# Convector_digit.net
KiCad netlist of a schematic drawn in Altium Designer
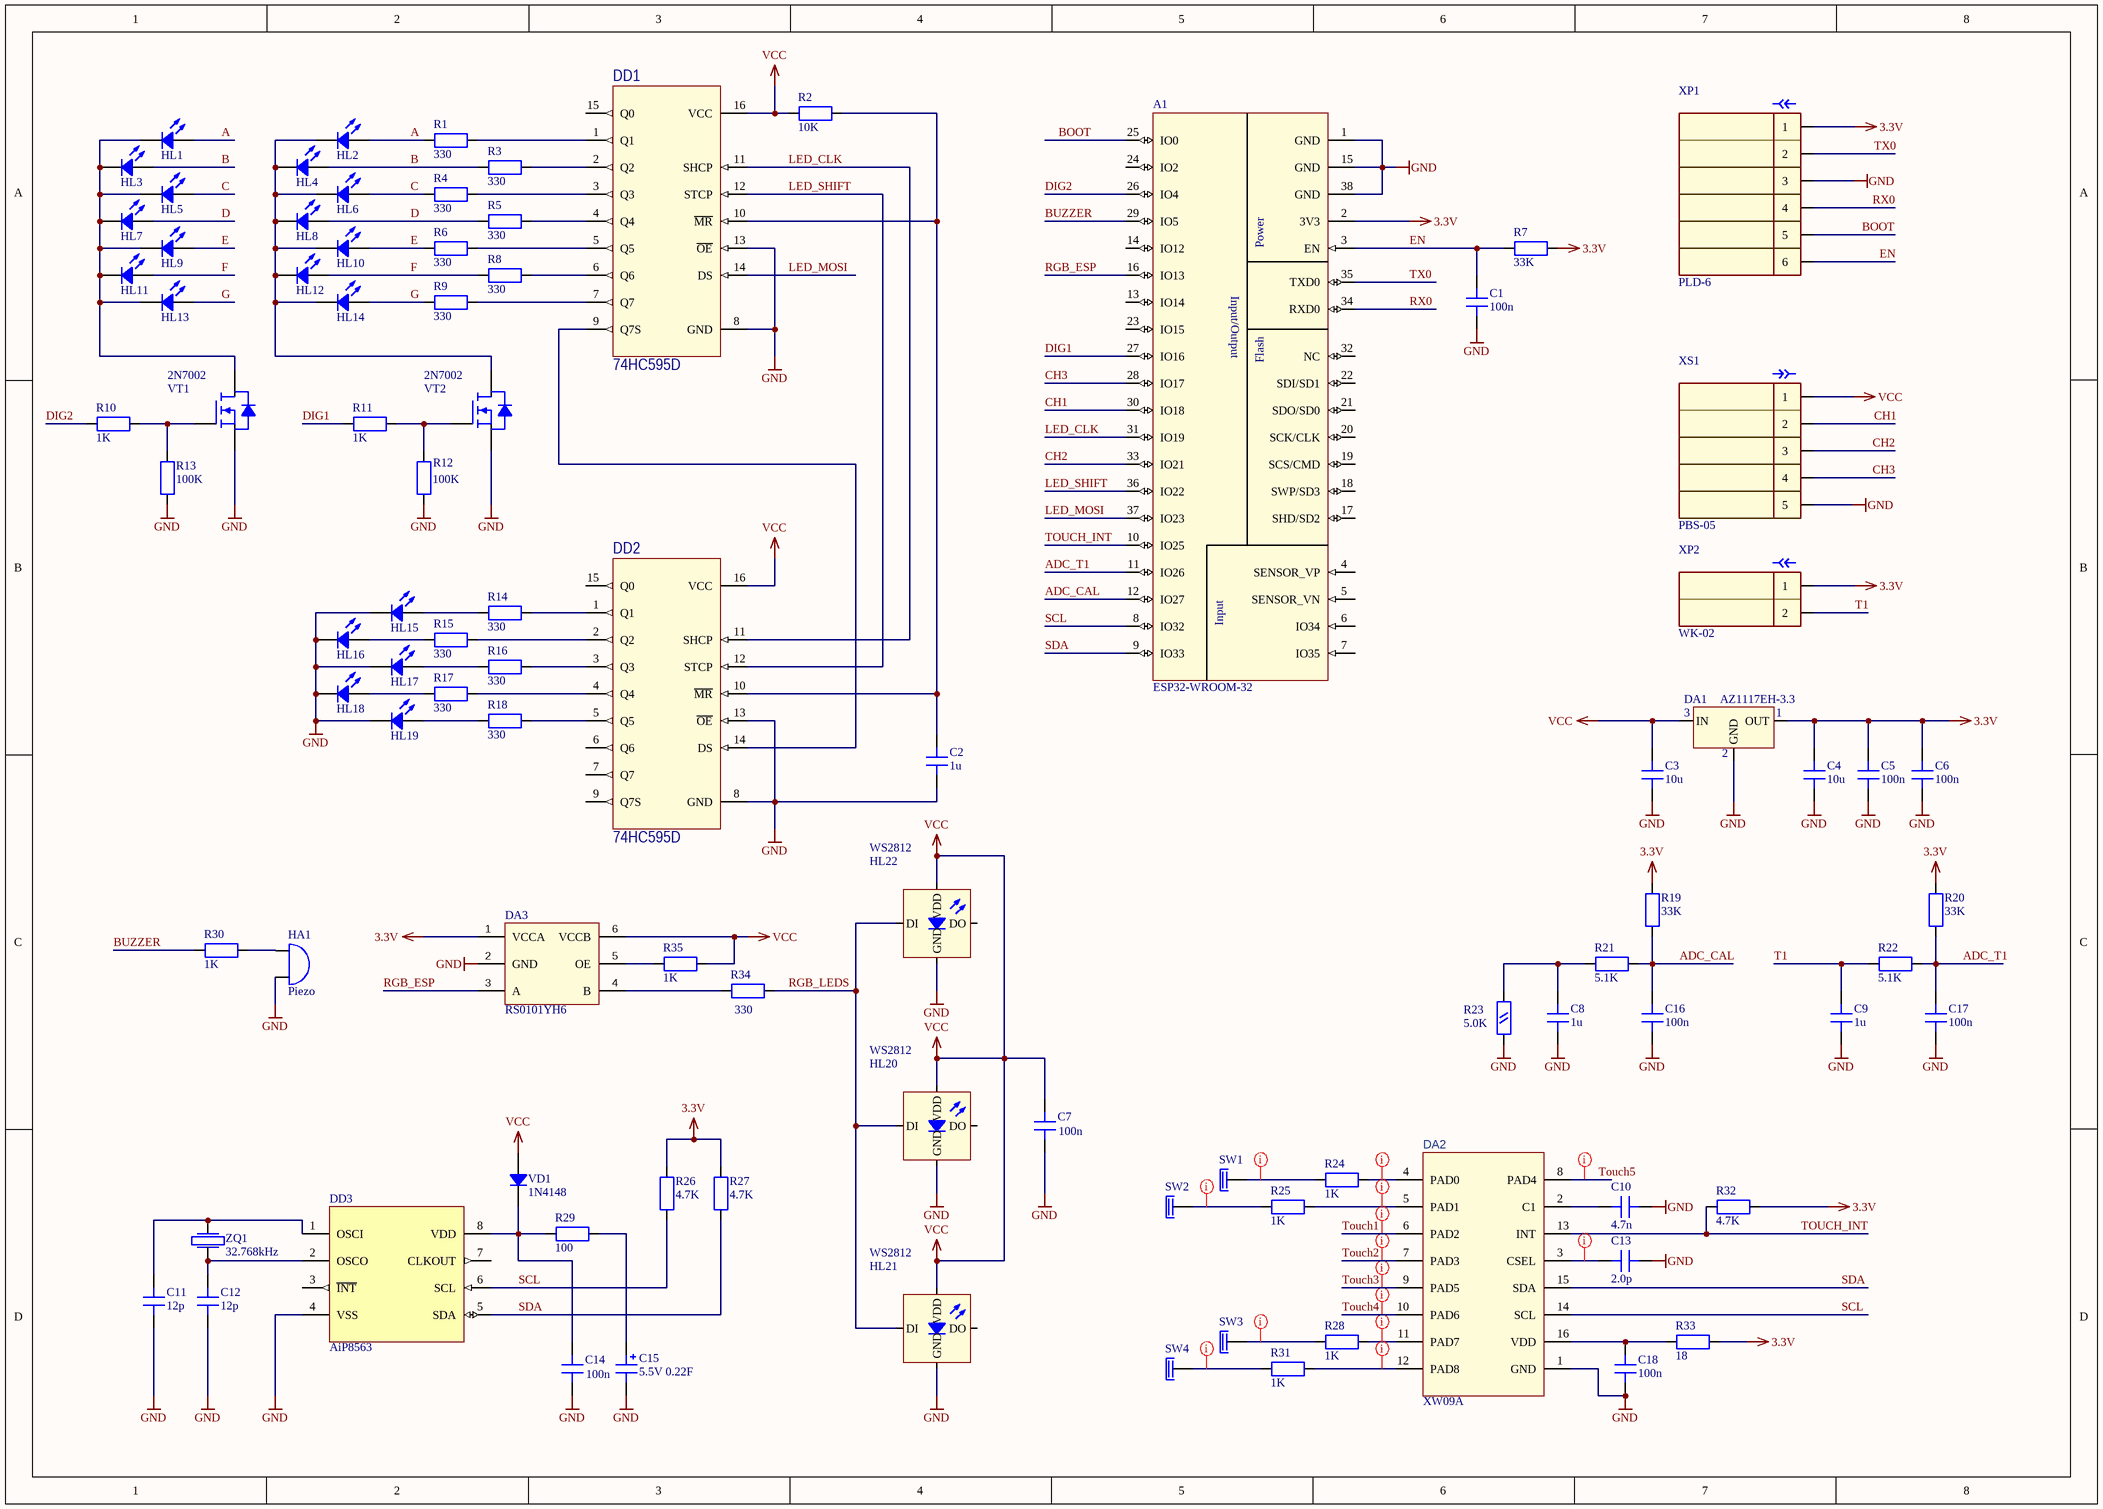
[diagram p0: Convector_digit.SchDoc]

(export (version "E")
  (design (tool "Eeschema 10.0.6"))
  (components
    (comp (ref "A1")
      (value "ESP32-WROOM-32")
      (footprint "ESP-WROOM-32")
      (fields (field (name "MANUFACTURER") "Espressif Systems"))
      (libsource (lib "IZTT_Library") (part "ESP32-WROOM-32"))
    )
    (comp (ref "C1")
      (value "100n")
      (footprint "C0603")
      (description "Cap Ceramic, 0603, ±10%, 50V, X7R (X5R), -55 +125C (-55 +85C)")
      (libsource (lib "IZTT_Library") (part "Capacitor"))
    )
    (comp (ref "C2")
      (value "1u")
      (footprint "C0603")
      (description "Cap Ceramic, 0603, ±10%, 50V, X7R (X5R), -55 +125C (-55 +85C)")
      (libsource (lib "IZTT_Library") (part "Capacitor"))
    )
    (comp (ref "C3")
      (value "10u")
      (footprint "C0805")
      (description "Cap Ceramic, 0805, ±10%, 50V, X7R (X5R), -55 +125C (-55 +85C)")
      (libsource (lib "IZTT_Library") (part "Capacitor"))
    )
    (comp (ref "C4")
      (value "10u")
      (footprint "C0805")
      (description "Cap Ceramic, 0805, ±10%, 50V, X7R (X5R), -55 +125C (-55 +85C)")
      (libsource (lib "IZTT_Library") (part "Capacitor"))
    )
    (comp (ref "C5")
      (value "100n")
      (footprint "C0603")
      (description "Cap Ceramic, 0603, ±10%, 50V, X7R (X5R), -55 +125C (-55 +85C)")
      (libsource (lib "IZTT_Library") (part "Capacitor"))
    )
    (comp (ref "C6")
      (value "100n")
      (footprint "C0603")
      (description "Cap Ceramic, 0603, ±10%, 50V, X7R (X5R), -55 +125C (-55 +85C)")
      (libsource (lib "IZTT_Library") (part "Capacitor"))
    )
    (comp (ref "C7")
      (value "100n")
      (footprint "C0603")
      (description "Cap Ceramic, 0603, ±10%, 50V, X7R (X5R), -55 +125C (-55 +85C)")
      (libsource (lib "IZTT_Library") (part "Capacitor"))
    )
    (comp (ref "C8")
      (value "1u")
      (footprint "C0603")
      (description "Cap Ceramic, 0603, ±10%, 50V, X7R (X5R), -55 +125C (-55 +85C)")
      (libsource (lib "IZTT_Library") (part "Capacitor"))
    )
    (comp (ref "C9")
      (value "1u")
      (footprint "C0603")
      (description "Cap Ceramic, 0603, ±10%, 50V, X7R (X5R), -55 +125C (-55 +85C)")
      (libsource (lib "IZTT_Library") (part "Capacitor"))
    )
    (comp (ref "C10")
      (value "4.7n")
      (footprint "C0603")
      (description "Cap Ceramic, 0603, ±10%, 50V, X7R (X5R), -55 +125C (-55 +85C)")
      (libsource (lib "IZTT_Library") (part "Capacitor"))
    )
    (comp (ref "C11")
      (value "12p")
      (footprint "C0603")
      (description "Cap Ceramic, 0603, 5%, 50V, NPO (C0G), -55 +125C")
      (libsource (lib "IZTT_Library") (part "Capacitor"))
    )
    (comp (ref "C12")
      (value "12p")
      (footprint "C0603")
      (description "Cap Ceramic, 0603, 5%, 50V, NPO (C0G), -55 +125C")
      (libsource (lib "IZTT_Library") (part "Capacitor"))
    )
    (comp (ref "C13")
      (value "2.0p")
      (footprint "C0603")
      (description "Cap Ceramic, 0603, 5%, 50V, NPO (C0G), -55 +125C")
      (libsource (lib "IZTT_Library") (part "Capacitor"))
    )
    (comp (ref "C14")
      (value "100n")
      (footprint "C0603")
      (description "Cap Ceramic, 0603, ±10%, 50V, X7R (X5R), -55 +125C (-55 +85C)")
      (libsource (lib "IZTT_Library") (part "Capacitor"))
    )
    (comp (ref "C15")
      (value "5.5V 0.22F")
      (footprint "1207H")
      (description "Ionistor 5.5V 0.22F")
      (fields (field (name "MANUFACTURER") "WTSCAP (Wenting)"))
      (libsource (lib "IZTT_Library") (part "Capacitor_polarised"))
    )
    (comp (ref "C16")
      (value "100n")
      (footprint "C0603")
      (description "Cap Ceramic, 0603, ±10%, 50V, X7R (X5R), -55 +125C (-55 +85C)")
      (libsource (lib "IZTT_Library") (part "Capacitor"))
    )
    (comp (ref "C17")
      (value "100n")
      (footprint "C0603")
      (description "Cap Ceramic, 0603, ±10%, 50V, X7R (X5R), -55 +125C (-55 +85C)")
      (libsource (lib "IZTT_Library") (part "Capacitor"))
    )
    (comp (ref "C18")
      (value "100n")
      (footprint "C0603")
      (description "Cap Ceramic, 0603, ±10%, 50V, X7R (X5R), -55 +125C (-55 +85C)")
      (libsource (lib "IZTT_Library") (part "Capacitor"))
    )
    (comp (ref "DA1")
      (value "AZ1117EH-3.3")
      (footprint "SOT-223")
      (description "IC, Vreg, LDO, For Low ESR MLCC Cout, SOT223")
      (libsource (lib "IZTT_Library") (part "LDO_1117"))
    )
    (comp (ref "DA2")
      (value "XW09A")
      (footprint "SO-16")
      (description "SOP-16 Touch Screen Controller ICs RoHS")
      (fields (field (name "MANUFACTURER") "Sam&wing") (field (name "LCSC_PARTNUMBER") "C441720"))
      (libsource (lib "IZTT_Library") (part "XW09X"))
    )
    (comp (ref "DA3")
      (value "RS0101YH6")
      (footprint "SOT-23-6")
      (description "Level Translators, Shifters RoHS")
      (fields (field (name "MANUFACTURER") "Jiangsu RUNIC Tech"))
      (libsource (lib "IZTT_Library") (part "RS0101YH6"))
    )
    (comp (ref "DD1")
      (value "74HC595D")
      (footprint "SO-16")
      (description "Shift Register Serial to parallel, serial SOIC-16_150mil")
      (fields (field (name "MANUFACTURER") "Shenzhen Fuman Elec"))
      (libsource (lib "IZTT_Library") (part "74HC595D"))
    )
    (comp (ref "DD2")
      (value "74HC595D")
      (footprint "SO-16")
      (description "Shift Register Serial to parallel, serial SOIC-16_150mil")
      (fields (field (name "MANUFACTURER") "Shenzhen Fuman Elec"))
      (libsource (lib "IZTT_Library") (part "74HC595D"))
    )
    (comp (ref "DD3")
      (value "AiP8563")
      (footprint "SO-8")
      (description "SOP-8 Real-time Clocks RoHS")
      (fields (field (name "MANUFACTURER") "Wuxi I-core Elec"))
      (libsource (lib "IZTT_Library") (part "AiP8563"))
    )
    (comp (ref "HA1")
      (value "Piezo")
      (footprint "PS1240P02BT")
      (description "BUZZER, Piezo, Pitch 5mm (TDK)")
      (libsource (lib "IZTT_Library") (part "Buzzer"))
    )
    (comp (ref "HL1")
      (value "0603 White")
      (footprint "LED0603Y")
      (description "LED, SMD 0603, 30mA, White")
      (fields (field (name "MANUFACTURER") "Orient"))
      (libsource (lib "IZTT_Library") (part "LED"))
    )
    (comp (ref "HL2")
      (value "0603 White")
      (footprint "LED0603Y")
      (description "LED, SMD 0603, 30mA, White")
      (fields (field (name "MANUFACTURER") "Orient"))
      (libsource (lib "IZTT_Library") (part "LED"))
    )
    (comp (ref "HL3")
      (value "0603 White")
      (footprint "LED0603Y")
      (description "LED, SMD 0603, 30mA, White")
      (fields (field (name "MANUFACTURER") "Orient"))
      (libsource (lib "IZTT_Library") (part "LED"))
    )
    (comp (ref "HL4")
      (value "0603 White")
      (footprint "LED0603Y")
      (description "LED, SMD 0603, 30mA, White")
      (fields (field (name "MANUFACTURER") "Orient"))
      (libsource (lib "IZTT_Library") (part "LED"))
    )
    (comp (ref "HL5")
      (value "0603 White")
      (footprint "LED0603Y")
      (description "LED, SMD 0603, 30mA, White")
      (fields (field (name "MANUFACTURER") "Orient"))
      (libsource (lib "IZTT_Library") (part "LED"))
    )
    (comp (ref "HL6")
      (value "0603 White")
      (footprint "LED0603Y")
      (description "LED, SMD 0603, 30mA, White")
      (fields (field (name "MANUFACTURER") "Orient"))
      (libsource (lib "IZTT_Library") (part "LED"))
    )
    (comp (ref "HL7")
      (value "0603 White")
      (footprint "LED0603Y")
      (description "LED, SMD 0603, 30mA, White")
      (fields (field (name "MANUFACTURER") "Orient"))
      (libsource (lib "IZTT_Library") (part "LED"))
    )
    (comp (ref "HL8")
      (value "0603 White")
      (footprint "LED0603Y")
      (description "LED, SMD 0603, 30mA, White")
      (fields (field (name "MANUFACTURER") "Orient"))
      (libsource (lib "IZTT_Library") (part "LED"))
    )
    (comp (ref "HL9")
      (value "0603 White")
      (footprint "LED0603Y")
      (description "LED, SMD 0603, 30mA, White")
      (fields (field (name "MANUFACTURER") "Orient"))
      (libsource (lib "IZTT_Library") (part "LED"))
    )
    (comp (ref "HL10")
      (value "0603 White")
      (footprint "LED0603Y")
      (description "LED, SMD 0603, 30mA, White")
      (fields (field (name "MANUFACTURER") "Orient"))
      (libsource (lib "IZTT_Library") (part "LED"))
    )
    (comp (ref "HL11")
      (value "0603 White")
      (footprint "LED0603Y")
      (description "LED, SMD 0603, 30mA, White")
      (fields (field (name "MANUFACTURER") "Orient"))
      (libsource (lib "IZTT_Library") (part "LED"))
    )
    (comp (ref "HL12")
      (value "0603 White")
      (footprint "LED0603Y")
      (description "LED, SMD 0603, 30mA, White")
      (fields (field (name "MANUFACTURER") "Orient"))
      (libsource (lib "IZTT_Library") (part "LED"))
    )
    (comp (ref "HL13")
      (value "0603 White")
      (footprint "LED0603Y")
      (description "LED, SMD 0603, 30mA, White")
      (fields (field (name "MANUFACTURER") "Orient"))
      (libsource (lib "IZTT_Library") (part "LED"))
    )
    (comp (ref "HL14")
      (value "0603 White")
      (footprint "LED0603Y")
      (description "LED, SMD 0603, 30mA, White")
      (fields (field (name "MANUFACTURER") "Orient"))
      (libsource (lib "IZTT_Library") (part "LED"))
    )
    (comp (ref "HL15")
      (value "0603 White")
      (footprint "LED0603Y")
      (description "LED, SMD 0603, 30mA, White")
      (fields (field (name "MANUFACTURER") "Orient"))
      (libsource (lib "IZTT_Library") (part "LED"))
    )
    (comp (ref "HL16")
      (value "0603 White")
      (footprint "LED0603Y")
      (description "LED, SMD 0603, 30mA, White")
      (fields (field (name "MANUFACTURER") "Orient"))
      (libsource (lib "IZTT_Library") (part "LED"))
    )
    (comp (ref "HL17")
      (value "0603 White")
      (footprint "LED0603Y")
      (description "LED, SMD 0603, 30mA, White")
      (fields (field (name "MANUFACTURER") "Orient"))
      (libsource (lib "IZTT_Library") (part "LED"))
    )
    (comp (ref "HL18")
      (value "0603 White")
      (footprint "LED0603Y")
      (description "LED, SMD 0603, 30mA, White")
      (fields (field (name "MANUFACTURER") "Orient"))
      (libsource (lib "IZTT_Library") (part "LED"))
    )
    (comp (ref "HL19")
      (value "0603 White")
      (footprint "LED0603Y")
      (description "LED, SMD 0603, 30mA, White")
      (fields (field (name "MANUFACTURER") "Orient"))
      (libsource (lib "IZTT_Library") (part "LED"))
    )
    (comp (ref "HL20")
      (value "WS2812")
      (footprint "WS2812C-2020")
      (description "Intelligent control LED, 2.0x2.0mm")
      (fields (field (name "MANUFACTURER") "Worldsemi"))
      (libsource (lib "IZTT_Library") (part "WS2812C-2020"))
    )
    (comp (ref "HL21")
      (value "WS2812")
      (footprint "WS2812C-2020")
      (description "Intelligent control LED, 2.0x2.0mm")
      (fields (field (name "MANUFACTURER") "Worldsemi"))
      (libsource (lib "IZTT_Library") (part "WS2812C-2020"))
    )
    (comp (ref "HL22")
      (value "WS2812")
      (footprint "WS2812C-2020")
      (description "Intelligent control LED, 2.0x2.0mm")
      (fields (field (name "MANUFACTURER") "Worldsemi"))
      (libsource (lib "IZTT_Library") (part "WS2812C-2020"))
    )
    (comp (ref "R1")
      (value "330")
      (footprint "R0603")
      (description "Res, 0603, 1%, 1/10W")
      (fields (field (name "MANUFACTURER") "Walsin Tech Corp"))
      (libsource (lib "IZTT_Library") (part "Resistor"))
    )
    (comp (ref "R2")
      (value "10K")
      (footprint "R0603")
      (description "Res, 0603, 1%, 1/10W")
      (fields (field (name "MANUFACTURER") "FH(Guangdong Fenghua Advanced Tech)"))
      (libsource (lib "IZTT_Library") (part "Resistor"))
    )
    (comp (ref "R3")
      (value "330")
      (footprint "R0603")
      (description "Res, 0603, 1%, 1/10W")
      (fields (field (name "MANUFACTURER") "Walsin Tech Corp"))
      (libsource (lib "IZTT_Library") (part "Resistor"))
    )
    (comp (ref "R4")
      (value "330")
      (footprint "R0603")
      (description "Res, 0603, 1%, 1/10W")
      (fields (field (name "MANUFACTURER") "Walsin Tech Corp"))
      (libsource (lib "IZTT_Library") (part "Resistor"))
    )
    (comp (ref "R5")
      (value "330")
      (footprint "R0603")
      (description "Res, 0603, 1%, 1/10W")
      (fields (field (name "MANUFACTURER") "Walsin Tech Corp"))
      (libsource (lib "IZTT_Library") (part "Resistor"))
    )
    (comp (ref "R6")
      (value "330")
      (footprint "R0603")
      (description "Res, 0603, 1%, 1/10W")
      (fields (field (name "MANUFACTURER") "Walsin Tech Corp"))
      (libsource (lib "IZTT_Library") (part "Resistor"))
    )
    (comp (ref "R7")
      (value "33K")
      (footprint "R0603")
      (description "Res, 0603, 1%, 1/10W")
      (fields (field (name "MANUFACTURER") "UNI-ROYAL(Uniroyal Elec)"))
      (libsource (lib "IZTT_Library") (part "Resistor"))
    )
    (comp (ref "R8")
      (value "330")
      (footprint "R0603")
      (description "Res, 0603, 1%, 1/10W")
      (fields (field (name "MANUFACTURER") "Walsin Tech Corp"))
      (libsource (lib "IZTT_Library") (part "Resistor"))
    )
    (comp (ref "R9")
      (value "330")
      (footprint "R0603")
      (description "Res, 0603, 1%, 1/10W")
      (fields (field (name "MANUFACTURER") "Walsin Tech Corp"))
      (libsource (lib "IZTT_Library") (part "Resistor"))
    )
    (comp (ref "R10")
      (value "1K")
      (footprint "R0603")
      (description "Res, 0603, 1%, 1/10W")
      (fields (field (name "MANUFACTURER") "FH(Guangdong Fenghua Advanced Tech)"))
      (libsource (lib "IZTT_Library") (part "Resistor"))
    )
    (comp (ref "R11")
      (value "1K")
      (footprint "R0603")
      (description "Res, 0603, 1%, 1/10W")
      (fields (field (name "MANUFACTURER") "FH(Guangdong Fenghua Advanced Tech)"))
      (libsource (lib "IZTT_Library") (part "Resistor"))
    )
    (comp (ref "R12")
      (value "100K")
      (footprint "R0603")
      (description "Res, 0603, 1%, 1/10W")
      (fields (field (name "MANUFACTURER") "UNI-ROYAL(Uniroyal Elec)"))
      (libsource (lib "IZTT_Library") (part "Resistor"))
    )
    (comp (ref "R13")
      (value "100K")
      (footprint "R0603")
      (description "Res, 0603, 1%, 1/10W")
      (fields (field (name "MANUFACTURER") "UNI-ROYAL(Uniroyal Elec)"))
      (libsource (lib "IZTT_Library") (part "Resistor"))
    )
    (comp (ref "R14")
      (value "330")
      (footprint "R0603")
      (description "Res, 0603, 1%, 1/10W")
      (fields (field (name "MANUFACTURER") "Walsin Tech Corp"))
      (libsource (lib "IZTT_Library") (part "Resistor"))
    )
    (comp (ref "R15")
      (value "330")
      (footprint "R0603")
      (description "Res, 0603, 1%, 1/10W")
      (fields (field (name "MANUFACTURER") "Walsin Tech Corp"))
      (libsource (lib "IZTT_Library") (part "Resistor"))
    )
    (comp (ref "R16")
      (value "330")
      (footprint "R0603")
      (description "Res, 0603, 1%, 1/10W")
      (fields (field (name "MANUFACTURER") "Walsin Tech Corp"))
      (libsource (lib "IZTT_Library") (part "Resistor"))
    )
    (comp (ref "R17")
      (value "330")
      (footprint "R0603")
      (description "Res, 0603, 1%, 1/10W")
      (fields (field (name "MANUFACTURER") "Walsin Tech Corp"))
      (libsource (lib "IZTT_Library") (part "Resistor"))
    )
    (comp (ref "R18")
      (value "330")
      (footprint "R0603")
      (description "Res, 0603, 1%, 1/10W")
      (fields (field (name "MANUFACTURER") "Walsin Tech Corp"))
      (libsource (lib "IZTT_Library") (part "Resistor"))
    )
    (comp (ref "R19")
      (value "33K")
      (footprint "R0603")
      (description "Res, 0603, 1%, 1/10W")
      (fields (field (name "MANUFACTURER") "UNI-ROYAL(Uniroyal Elec)"))
      (libsource (lib "IZTT_Library") (part "Resistor"))
    )
    (comp (ref "R20")
      (value "33K")
      (footprint "R0603")
      (description "Res, 0603, 1%, 1/10W")
      (fields (field (name "MANUFACTURER") "UNI-ROYAL(Uniroyal Elec)"))
      (libsource (lib "IZTT_Library") (part "Resistor"))
    )
    (comp (ref "R21")
      (value "5.1K")
      (footprint "R0603")
      (description "Res, 0603, 1%, 1/10W")
      (libsource (lib "IZTT_Library") (part "Resistor"))
    )
    (comp (ref "R22")
      (value "5.1K")
      (footprint "R0603")
      (description "Res, 0603, 1%, 1/10W")
      (libsource (lib "IZTT_Library") (part "Resistor"))
    )
    (comp (ref "R23")
      (value "5.0K")
      (footprint "R0805")
      (description "Res, 0805, 0.1%, 1/8W")
      (libsource (lib "IZTT_Library") (part "Resistor_1/8W"))
    )
    (comp (ref "R24")
      (value "1K")
      (footprint "R0603")
      (description "Res, 0603, 1%, 1/10W")
      (fields (field (name "MANUFACTURER") "FH(Guangdong Fenghua Advanced Tech)"))
      (libsource (lib "IZTT_Library") (part "Resistor"))
    )
    (comp (ref "R25")
      (value "1K")
      (footprint "R0603")
      (description "Res, 0603, 1%, 1/10W")
      (fields (field (name "MANUFACTURER") "FH(Guangdong Fenghua Advanced Tech)"))
      (libsource (lib "IZTT_Library") (part "Resistor"))
    )
    (comp (ref "R26")
      (value "4.7K")
      (footprint "R0603")
      (description "Res, 0603, 1%, 1/10W")
      (fields (field (name "MANUFACTURER") "UNI-ROYAL(Uniroyal Elec)"))
      (libsource (lib "IZTT_Library") (part "Resistor"))
    )
    (comp (ref "R27")
      (value "4.7K")
      (footprint "R0603")
      (description "Res, 0603, 1%, 1/10W")
      (fields (field (name "MANUFACTURER") "UNI-ROYAL(Uniroyal Elec)"))
      (libsource (lib "IZTT_Library") (part "Resistor"))
    )
    (comp (ref "R28")
      (value "1K")
      (footprint "R0603")
      (description "Res, 0603, 1%, 1/10W")
      (fields (field (name "MANUFACTURER") "FH(Guangdong Fenghua Advanced Tech)"))
      (libsource (lib "IZTT_Library") (part "Resistor"))
    )
    (comp (ref "R29")
      (value "100")
      (footprint "R0603")
      (description "Res, 0603, 1%, 1/10W")
      (fields (field (name "MANUFACTURER") "UNI-ROYAL(Uniroyal Elec)"))
      (libsource (lib "IZTT_Library") (part "Resistor"))
    )
    (comp (ref "R30")
      (value "1K")
      (footprint "R0603")
      (description "Res, 0603, 1%, 1/10W")
      (fields (field (name "MANUFACTURER") "FH(Guangdong Fenghua Advanced Tech)"))
      (libsource (lib "IZTT_Library") (part "Resistor"))
    )
    (comp (ref "R31")
      (value "1K")
      (footprint "R0603")
      (description "Res, 0603, 1%, 1/10W")
      (fields (field (name "MANUFACTURER") "FH(Guangdong Fenghua Advanced Tech)"))
      (libsource (lib "IZTT_Library") (part "Resistor"))
    )
    (comp (ref "R32")
      (value "4.7K")
      (footprint "R0603")
      (description "Res, 0603, 1%, 1/10W")
      (fields (field (name "MANUFACTURER") "UNI-ROYAL(Uniroyal Elec)"))
      (libsource (lib "IZTT_Library") (part "Resistor"))
    )
    (comp (ref "R33")
      (value "18")
      (footprint "R0603")
      (description "Res, 0603, 1%, 1/10W")
      (libsource (lib "IZTT_Library") (part "Resistor"))
    )
    (comp (ref "R34")
      (value "330")
      (footprint "R0603")
      (description "Res, 0603, 1%, 1/10W")
      (fields (field (name "MANUFACTURER") "Walsin Tech Corp"))
      (libsource (lib "IZTT_Library") (part "Resistor"))
    )
    (comp (ref "R35")
      (value "1K")
      (footprint "R0603")
      (description "Res, 0603, 1%, 1/10W")
      (fields (field (name "MANUFACTURER") "FH(Guangdong Fenghua Advanced Tech)"))
      (libsource (lib "IZTT_Library") (part "Resistor"))
    )
    (comp (ref "SW1")
      (value "XL-2258")
      (footprint "XL-2258")
      (description "Sensor Spring D=5.5/8.5, H=8.5±0.5mm")
      (libsource (lib "IZTT_Library") (part "SENSOR_SPRING"))
    )
    (comp (ref "SW2")
      (value "XL-2258")
      (footprint "XL-2258")
      (description "Sensor Spring D=5.5/8.5, H=8.5±0.5mm")
      (libsource (lib "IZTT_Library") (part "SENSOR_SPRING"))
    )
    (comp (ref "SW3")
      (value "XL-2258")
      (footprint "XL-2258")
      (description "Sensor Spring D=5.5/8.5, H=8.5±0.5mm")
      (libsource (lib "IZTT_Library") (part "SENSOR_SPRING"))
    )
    (comp (ref "SW4")
      (value "XL-2258")
      (footprint "XL-2258")
      (description "Sensor Spring D=5.5/8.5, H=8.5±0.5mm")
      (libsource (lib "IZTT_Library") (part "SENSOR_SPRING"))
    )
    (comp (ref "VD1")
      (value "1N4148")
      (footprint "SOD-323_DIODE")
      (description "Small Signal Fast Switching Diode, 150mA, 75V")
      (libsource (lib "IZTT_Library") (part "Diode"))
    )
    (comp (ref "VT1")
      (value "2N7002")
      (footprint "SOT-23-3")
      (description "HEXFET Power MOSFET N-CH")
      (libsource (lib "IZTT_Library") (part "N-MOS"))
    )
    (comp (ref "VT2")
      (value "2N7002")
      (footprint "SOT-23-3")
      (description "HEXFET Power MOSFET N-CH")
      (libsource (lib "IZTT_Library") (part "N-MOS"))
    )
    (comp (ref "XP1")
      (value "PLD-6")
      (footprint "PLD-6")
      (description "2x3 Male pld pins 2.54")
      (libsource (lib "IZTT_Library") (part "MALE_6PIN"))
    )
    (comp (ref "XP2")
      (value "WK-02")
      (footprint "WK-02")
      (description "Through-hole type shrouded header, XH Series, 2.5mm")
      (libsource (lib "IZTT_Library") (part "MALE_2PIN"))
    )
    (comp (ref "XS1")
      (value "PBS-05")
      (footprint "PBS-05")
      (description "Through-hole type shrouded header, XH Series, 2.5mm")
      (libsource (lib "IZTT_Library") (part "FEMALE_5PIN"))
    )
    (comp (ref "ZQ1")
      (value "32.768kHz")
      (footprint "KX-327NHT")
      (description "Quartz 32.768kHz 12.5pF 20ppm")
      (libsource (lib "IZTT_Library") (part "QUARTZ"))
    )
  )
  (nets
    (net (code "1") (name "/A") (class "Default")
      (node (ref "HL1") (pin "A") (pinfunction "A_A") (pintype "passive"))
      (node (ref "HL2") (pin "A") (pinfunction "A_A") (pintype "passive"))
      (node (ref "R1") (pin "1") (pinfunction "1_1") (pintype "passive"))
    )
    (net (code "2") (name "/ADC_CAL") (class "Default")
      (node (ref "A1") (pin "12") (pinfunction "IO27_12") (pintype "bidirectional"))
      (node (ref "C16") (pin "2") (pinfunction "2_2") (pintype "passive"))
      (node (ref "R19") (pin "1") (pinfunction "1_1") (pintype "passive"))
      (node (ref "R21") (pin "2") (pinfunction "2_2") (pintype "passive"))
    )
    (net (code "3") (name "/ADC_T1") (class "Default")
      (node (ref "A1") (pin "11") (pinfunction "IO26_11") (pintype "bidirectional"))
      (node (ref "C17") (pin "2") (pinfunction "2_2") (pintype "passive"))
      (node (ref "R20") (pin "1") (pinfunction "1_1") (pintype "passive"))
      (node (ref "R22") (pin "2") (pinfunction "2_2") (pintype "passive"))
    )
    (net (code "4") (name "/B") (class "Default")
      (node (ref "HL3") (pin "A") (pinfunction "A_A") (pintype "passive"))
      (node (ref "HL4") (pin "A") (pinfunction "A_A") (pintype "passive"))
      (node (ref "R3") (pin "1") (pinfunction "1_1") (pintype "passive"))
    )
    (net (code "5") (name "/BOOT") (class "Default")
      (node (ref "A1") (pin "25") (pinfunction "IO0_25") (pintype "bidirectional"))
      (node (ref "XP1") (pin "5") (pinfunction "5_5") (pintype "passive"))
    )
    (net (code "6") (name "/BUZZER") (class "Default")
      (node (ref "A1") (pin "29") (pinfunction "IO5_29") (pintype "bidirectional"))
      (node (ref "R30") (pin "2") (pinfunction "2_2") (pintype "passive"))
    )
    (net (code "7") (name "/C") (class "Default")
      (node (ref "HL5") (pin "A") (pinfunction "A_A") (pintype "passive"))
      (node (ref "HL6") (pin "A") (pinfunction "A_A") (pintype "passive"))
      (node (ref "R4") (pin "1") (pinfunction "1_1") (pintype "passive"))
    )
    (net (code "8") (name "/CH1") (class "Default")
      (node (ref "A1") (pin "30") (pinfunction "IO18_30") (pintype "bidirectional"))
      (node (ref "XS1") (pin "2") (pinfunction "2_2") (pintype "passive"))
    )
    (net (code "9") (name "/CH2") (class "Default")
      (node (ref "A1") (pin "33") (pinfunction "IO21_33") (pintype "bidirectional"))
      (node (ref "XS1") (pin "3") (pinfunction "3_3") (pintype "passive"))
    )
    (net (code "10") (name "/CH3") (class "Default")
      (node (ref "A1") (pin "28") (pinfunction "IO17_28") (pintype "bidirectional"))
      (node (ref "XS1") (pin "4") (pinfunction "4_4") (pintype "passive"))
    )
    (net (code "11") (name "/D") (class "Default")
      (node (ref "HL7") (pin "A") (pinfunction "A_A") (pintype "passive"))
      (node (ref "HL8") (pin "A") (pinfunction "A_A") (pintype "passive"))
      (node (ref "R5") (pin "1") (pinfunction "1_1") (pintype "passive"))
    )
    (net (code "12") (name "/DIG1") (class "Default")
      (node (ref "A1") (pin "27") (pinfunction "IO16_27") (pintype "bidirectional"))
      (node (ref "R11") (pin "2") (pinfunction "2_2") (pintype "passive"))
    )
    (net (code "13") (name "/DIG2") (class "Default")
      (node (ref "A1") (pin "26") (pinfunction "IO4_26") (pintype "bidirectional"))
      (node (ref "R10") (pin "2") (pinfunction "2_2") (pintype "passive"))
    )
    (net (code "14") (name "/E") (class "Default")
      (node (ref "HL10") (pin "A") (pinfunction "A_A") (pintype "passive"))
      (node (ref "HL9") (pin "A") (pinfunction "A_A") (pintype "passive"))
      (node (ref "R6") (pin "1") (pinfunction "1_1") (pintype "passive"))
    )
    (net (code "15") (name "/EN") (class "Default")
      (node (ref "A1") (pin "3") (pinfunction "EN_3") (pintype "input"))
      (node (ref "C1") (pin "2") (pinfunction "2_2") (pintype "passive"))
      (node (ref "R7") (pin "1") (pinfunction "1_1") (pintype "passive"))
      (node (ref "XP1") (pin "6") (pinfunction "6_6") (pintype "passive"))
    )
    (net (code "16") (name "/F") (class "Default")
      (node (ref "HL11") (pin "A") (pinfunction "A_A") (pintype "passive"))
      (node (ref "HL12") (pin "A") (pinfunction "A_A") (pintype "passive"))
      (node (ref "R8") (pin "1") (pinfunction "1_1") (pintype "passive"))
    )
    (net (code "17") (name "/G") (class "Default")
      (node (ref "HL13") (pin "A") (pinfunction "A_A") (pintype "passive"))
      (node (ref "HL14") (pin "A") (pinfunction "A_A") (pintype "passive"))
      (node (ref "R9") (pin "1") (pinfunction "1_1") (pintype "passive"))
    )
    (net (code "18") (name "/LED_CLK") (class "Default")
      (node (ref "A1") (pin "31") (pinfunction "IO19_31") (pintype "bidirectional"))
      (node (ref "DD1") (pin "11") (pinfunction "SHCP_11") (pintype "input"))
      (node (ref "DD2") (pin "11") (pinfunction "SHCP_11") (pintype "input"))
    )
    (net (code "19") (name "/LED_MOSI") (class "Default")
      (node (ref "A1") (pin "37") (pinfunction "IO23_37") (pintype "bidirectional"))
      (node (ref "DD1") (pin "14") (pinfunction "DS_14") (pintype "input"))
    )
    (net (code "20") (name "/LED_SHIFT") (class "Default")
      (node (ref "A1") (pin "36") (pinfunction "IO22_36") (pintype "bidirectional"))
      (node (ref "DD1") (pin "12") (pinfunction "STCP_12") (pintype "input"))
      (node (ref "DD2") (pin "12") (pinfunction "STCP_12") (pintype "input"))
    )
    (net (code "21") (name "/RGB_ESP") (class "Default")
      (node (ref "A1") (pin "16") (pinfunction "IO13_16") (pintype "bidirectional"))
      (node (ref "DA3") (pin "3") (pinfunction "A_3") (pintype "passive"))
    )
    (net (code "22") (name "/RGB_LEDS") (class "Default")
      (node (ref "HL20") (pin "I") (pinfunction "DI_I") (pintype "passive"))
      (node (ref "HL21") (pin "I") (pinfunction "DI_I") (pintype "passive"))
      (node (ref "HL22") (pin "I") (pinfunction "DI_I") (pintype "passive"))
      (node (ref "R34") (pin "2") (pinfunction "2_2") (pintype "passive"))
    )
    (net (code "23") (name "/RX0") (class "Default")
      (node (ref "A1") (pin "34") (pinfunction "RXD0_34") (pintype "bidirectional"))
      (node (ref "XP1") (pin "4") (pinfunction "4_4") (pintype "passive"))
    )
    (net (code "24") (name "/SCL") (class "Default")
      (node (ref "A1") (pin "8") (pinfunction "IO32_8") (pintype "bidirectional"))
      (node (ref "DA2") (pin "14") (pinfunction "SCL_14") (pintype "passive"))
      (node (ref "DD3") (pin "6") (pinfunction "SCL_6") (pintype "input"))
      (node (ref "R26") (pin "1") (pinfunction "1_1") (pintype "passive"))
    )
    (net (code "25") (name "/SDA") (class "Default")
      (node (ref "A1") (pin "9") (pinfunction "IO33_9") (pintype "bidirectional"))
      (node (ref "DA2") (pin "15") (pinfunction "SDA_15") (pintype "passive"))
      (node (ref "DD3") (pin "5") (pinfunction "SDA_5") (pintype "bidirectional"))
      (node (ref "R27") (pin "1") (pinfunction "1_1") (pintype "passive"))
    )
    (net (code "26") (name "/T1") (class "Default")
      (node (ref "C9") (pin "2") (pinfunction "2_2") (pintype "passive"))
      (node (ref "R22") (pin "1") (pinfunction "1_1") (pintype "passive"))
      (node (ref "XP2") (pin "2") (pinfunction "2_2") (pintype "passive"))
    )
    (net (code "27") (name "/TOUCH_INT") (class "Default")
      (node (ref "A1") (pin "10") (pinfunction "IO25_10") (pintype "bidirectional"))
      (node (ref "DA2") (pin "13") (pinfunction "INT_13") (pintype "passive"))
      (node (ref "R32") (pin "1") (pinfunction "1_1") (pintype "passive"))
    )
    (net (code "28") (name "/TX0") (class "Default")
      (node (ref "A1") (pin "35") (pinfunction "TXD0_35") (pintype "bidirectional"))
      (node (ref "XP1") (pin "2") (pinfunction "2_2") (pintype "passive"))
    )
    (net (code "29") (name "/Touch1") (class "Default")
      (node (ref "DA2") (pin "6") (pinfunction "PAD2_6") (pintype "passive"))
    )
    (net (code "30") (name "/Touch2") (class "Default")
      (node (ref "DA2") (pin "7") (pinfunction "PAD3_7") (pintype "passive"))
    )
    (net (code "31") (name "/Touch3") (class "Default")
      (node (ref "DA2") (pin "9") (pinfunction "PAD5_9") (pintype "passive"))
    )
    (net (code "32") (name "/Touch4") (class "Default")
      (node (ref "DA2") (pin "10") (pinfunction "PAD6_10") (pintype "passive"))
    )
    (net (code "33") (name "/Touch5") (class "Default")
      (node (ref "DA2") (pin "8") (pinfunction "PAD4_8") (pintype "passive"))
    )
    (net (code "34") (name "3.3V") (class "Default")
      (node (ref "A1") (pin "2") (pinfunction "3V3_2") (pintype "power_in"))
      (node (ref "C4") (pin "2") (pinfunction "2_2") (pintype "passive"))
      (node (ref "C5") (pin "2") (pinfunction "2_2") (pintype "passive"))
      (node (ref "C6") (pin "2") (pinfunction "2_2") (pintype "passive"))
      (node (ref "DA1") (pin "Y") (pinfunction "OUT_Y") (pintype "passive"))
      (node (ref "DA3") (pin "1") (pinfunction "VCCA_1") (pintype "passive"))
      (node (ref "R19") (pin "2") (pinfunction "2_2") (pintype "passive"))
      (node (ref "R20") (pin "2") (pinfunction "2_2") (pintype "passive"))
      (node (ref "R26") (pin "2") (pinfunction "2_2") (pintype "passive"))
      (node (ref "R27") (pin "2") (pinfunction "2_2") (pintype "passive"))
      (node (ref "R32") (pin "2") (pinfunction "2_2") (pintype "passive"))
      (node (ref "R33") (pin "2") (pinfunction "2_2") (pintype "passive"))
      (node (ref "R7") (pin "2") (pinfunction "2_2") (pintype "passive"))
      (node (ref "XP1") (pin "1") (pinfunction "1_1") (pintype "passive"))
      (node (ref "XP2") (pin "1") (pinfunction "1_1") (pintype "passive"))
    )
    (net (code "35") (name "GND") (class "Default")
      (node (ref "A1") (pin "1") (pinfunction "GND_1") (pintype "power_in"))
      (node (ref "A1") (pin "15") (pinfunction "GND_15") (pintype "power_in"))
      (node (ref "A1") (pin "38") (pinfunction "GND_38") (pintype "power_in"))
      (node (ref "C1") (pin "1") (pinfunction "1_1") (pintype "passive"))
      (node (ref "C10") (pin "2") (pinfunction "2_2") (pintype "passive"))
      (node (ref "C11") (pin "1") (pinfunction "1_1") (pintype "passive"))
      (node (ref "C12") (pin "1") (pinfunction "1_1") (pintype "passive"))
      (node (ref "C13") (pin "2") (pinfunction "2_2") (pintype "passive"))
      (node (ref "C14") (pin "2") (pinfunction "2_2") (pintype "passive"))
      (node (ref "C15") (pin "-") (pinfunction "-_-") (pintype "passive"))
      (node (ref "C16") (pin "1") (pinfunction "1_1") (pintype "passive"))
      (node (ref "C17") (pin "1") (pinfunction "1_1") (pintype "passive"))
      (node (ref "C18") (pin "1") (pinfunction "1_1") (pintype "passive"))
      (node (ref "C2") (pin "1") (pinfunction "1_1") (pintype "passive"))
      (node (ref "C3") (pin "1") (pinfunction "1_1") (pintype "passive"))
      (node (ref "C4") (pin "1") (pinfunction "1_1") (pintype "passive"))
      (node (ref "C5") (pin "1") (pinfunction "1_1") (pintype "passive"))
      (node (ref "C6") (pin "1") (pinfunction "1_1") (pintype "passive"))
      (node (ref "C7") (pin "1") (pinfunction "1_1") (pintype "passive"))
      (node (ref "C8") (pin "1") (pinfunction "1_1") (pintype "passive"))
      (node (ref "C9") (pin "1") (pinfunction "1_1") (pintype "passive"))
      (node (ref "DA1") (pin "X") (pinfunction "GND_X") (pintype "passive"))
      (node (ref "DA2") (pin "1") (pinfunction "GND_1") (pintype "passive"))
      (node (ref "DA3") (pin "2") (pinfunction "GND_2") (pintype "passive"))
      (node (ref "DD1") (pin "13") (pinfunction "~{OE}_13") (pintype "input"))
      (node (ref "DD1") (pin "8") (pinfunction "GND_8") (pintype "power_in"))
      (node (ref "DD2") (pin "13") (pinfunction "~{OE}_13") (pintype "input"))
      (node (ref "DD2") (pin "8") (pinfunction "GND_8") (pintype "power_in"))
      (node (ref "DD3") (pin "4") (pinfunction "VSS_4") (pintype "power_in"))
      (node (ref "HA1") (pin "2") (pintype "passive"))
      (node (ref "HL15") (pin "C") (pinfunction "C_C") (pintype "passive"))
      (node (ref "HL16") (pin "C") (pinfunction "C_C") (pintype "passive"))
      (node (ref "HL17") (pin "C") (pinfunction "C_C") (pintype "passive"))
      (node (ref "HL18") (pin "C") (pinfunction "C_C") (pintype "passive"))
      (node (ref "HL19") (pin "C") (pinfunction "C_C") (pintype "passive"))
      (node (ref "HL20") (pin "-") (pinfunction "GND_-") (pintype "passive"))
      (node (ref "HL21") (pin "-") (pinfunction "GND_-") (pintype "passive"))
      (node (ref "HL22") (pin "-") (pinfunction "GND_-") (pintype "passive"))
      (node (ref "R12") (pin "1") (pinfunction "1_1") (pintype "passive"))
      (node (ref "R13") (pin "1") (pinfunction "1_1") (pintype "passive"))
      (node (ref "R23") (pin "1") (pinfunction "1_1") (pintype "passive"))
      (node (ref "VT1") (pin "Z") (pinfunction "S_Z") (pintype "passive"))
      (node (ref "VT2") (pin "Z") (pinfunction "S_Z") (pintype "passive"))
      (node (ref "XP1") (pin "3") (pinfunction "3_3") (pintype "passive"))
      (node (ref "XS1") (pin "5") (pinfunction "5_5") (pintype "passive"))
    )
    (net (code "36") (name "Net-(C8-Pad2)") (class "Default")
      (node (ref "C8") (pin "2") (pinfunction "2_2") (pintype "passive"))
      (node (ref "R21") (pin "1") (pinfunction "1_1") (pintype "passive"))
      (node (ref "R23") (pin "2") (pinfunction "2_2") (pintype "passive"))
    )
    (net (code "37") (name "Net-(C15-Pad+)") (class "Default")
      (node (ref "C15") (pin "+") (pinfunction "+_+") (pintype "passive"))
      (node (ref "R29") (pin "2") (pinfunction "2_2") (pintype "passive"))
    )
    (net (code "38") (name "Net-(DA2-C1)") (class "Default")
      (node (ref "C10") (pin "1") (pinfunction "1_1") (pintype "passive"))
      (node (ref "DA2") (pin "2") (pinfunction "C1_2") (pintype "passive"))
    )
    (net (code "39") (name "Net-(DA2-CSEL)") (class "Default")
      (node (ref "C13") (pin "1") (pinfunction "1_1") (pintype "passive"))
      (node (ref "DA2") (pin "3") (pinfunction "CSEL_3") (pintype "passive"))
    )
    (net (code "40") (name "Net-(DA2-PAD0)") (class "Default")
      (node (ref "DA2") (pin "4") (pinfunction "PAD0_4") (pintype "passive"))
      (node (ref "R24") (pin "2") (pinfunction "2_2") (pintype "passive"))
    )
    (net (code "41") (name "Net-(DA2-PAD1)") (class "Default")
      (node (ref "DA2") (pin "5") (pinfunction "PAD1_5") (pintype "passive"))
      (node (ref "R25") (pin "2") (pinfunction "2_2") (pintype "passive"))
    )
    (net (code "42") (name "Net-(DA2-PAD7)") (class "Default")
      (node (ref "DA2") (pin "11") (pinfunction "PAD7_11") (pintype "passive"))
      (node (ref "R28") (pin "2") (pinfunction "2_2") (pintype "passive"))
    )
    (net (code "43") (name "Net-(DA2-PAD8)") (class "Default")
      (node (ref "DA2") (pin "12") (pinfunction "PAD8_12") (pintype "passive"))
      (node (ref "R31") (pin "2") (pinfunction "2_2") (pintype "passive"))
    )
    (net (code "44") (name "Net-(DA2-VDD)") (class "Default")
      (node (ref "C18") (pin "2") (pinfunction "2_2") (pintype "passive"))
      (node (ref "DA2") (pin "16") (pinfunction "VDD_16") (pintype "passive"))
      (node (ref "R33") (pin "1") (pinfunction "1_1") (pintype "passive"))
    )
    (net (code "45") (name "Net-(DA3-B)") (class "Default")
      (node (ref "DA3") (pin "4") (pinfunction "B_4") (pintype "passive"))
      (node (ref "R34") (pin "1") (pinfunction "1_1") (pintype "passive"))
    )
    (net (code "46") (name "Net-(DA3-OE)") (class "Default")
      (node (ref "DA3") (pin "5") (pinfunction "OE_5") (pintype "passive"))
      (node (ref "R35") (pin "1") (pinfunction "1_1") (pintype "passive"))
    )
    (net (code "47") (name "Net-(DD1-Q1)") (class "Default")
      (node (ref "DD1") (pin "1") (pinfunction "Q1_1") (pintype "output"))
      (node (ref "R1") (pin "2") (pinfunction "2_2") (pintype "passive"))
    )
    (net (code "48") (name "Net-(DD1-Q2)") (class "Default")
      (node (ref "DD1") (pin "2") (pinfunction "Q2_2") (pintype "output"))
      (node (ref "R3") (pin "2") (pinfunction "2_2") (pintype "passive"))
    )
    (net (code "49") (name "Net-(DD1-Q3)") (class "Default")
      (node (ref "DD1") (pin "3") (pinfunction "Q3_3") (pintype "output"))
      (node (ref "R4") (pin "2") (pinfunction "2_2") (pintype "passive"))
    )
    (net (code "50") (name "Net-(DD1-Q4)") (class "Default")
      (node (ref "DD1") (pin "4") (pinfunction "Q4_4") (pintype "output"))
      (node (ref "R5") (pin "2") (pinfunction "2_2") (pintype "passive"))
    )
    (net (code "51") (name "Net-(DD1-Q5)") (class "Default")
      (node (ref "DD1") (pin "5") (pinfunction "Q5_5") (pintype "output"))
      (node (ref "R6") (pin "2") (pinfunction "2_2") (pintype "passive"))
    )
    (net (code "52") (name "Net-(DD1-Q6)") (class "Default")
      (node (ref "DD1") (pin "6") (pinfunction "Q6_6") (pintype "output"))
      (node (ref "R8") (pin "2") (pinfunction "2_2") (pintype "passive"))
    )
    (net (code "53") (name "Net-(DD1-Q7)") (class "Default")
      (node (ref "DD1") (pin "7") (pinfunction "Q7_7") (pintype "output"))
      (node (ref "R9") (pin "2") (pinfunction "2_2") (pintype "passive"))
    )
    (net (code "54") (name "Net-(DD1-Q7S)") (class "Default")
      (node (ref "DD1") (pin "9") (pinfunction "Q7S_9") (pintype "output"))
      (node (ref "DD2") (pin "14") (pinfunction "DS_14") (pintype "input"))
    )
    (net (code "55") (name "Net-(DD1-~{MR})") (class "Default")
      (node (ref "C2") (pin "2") (pinfunction "2_2") (pintype "passive"))
      (node (ref "DD1") (pin "10") (pinfunction "~{MR}_10") (pintype "input"))
      (node (ref "DD2") (pin "10") (pinfunction "~{MR}_10") (pintype "input"))
      (node (ref "R2") (pin "2") (pinfunction "2_2") (pintype "passive"))
    )
    (net (code "56") (name "Net-(DD2-Q1)") (class "Default")
      (node (ref "DD2") (pin "1") (pinfunction "Q1_1") (pintype "output"))
      (node (ref "R14") (pin "2") (pinfunction "2_2") (pintype "passive"))
    )
    (net (code "57") (name "Net-(DD2-Q2)") (class "Default")
      (node (ref "DD2") (pin "2") (pinfunction "Q2_2") (pintype "output"))
      (node (ref "R15") (pin "2") (pinfunction "2_2") (pintype "passive"))
    )
    (net (code "58") (name "Net-(DD2-Q3)") (class "Default")
      (node (ref "DD2") (pin "3") (pinfunction "Q3_3") (pintype "output"))
      (node (ref "R16") (pin "2") (pinfunction "2_2") (pintype "passive"))
    )
    (net (code "59") (name "Net-(DD2-Q4)") (class "Default")
      (node (ref "DD2") (pin "4") (pinfunction "Q4_4") (pintype "output"))
      (node (ref "R17") (pin "2") (pinfunction "2_2") (pintype "passive"))
    )
    (net (code "60") (name "Net-(DD2-Q5)") (class "Default")
      (node (ref "DD2") (pin "5") (pinfunction "Q5_5") (pintype "output"))
      (node (ref "R18") (pin "2") (pinfunction "2_2") (pintype "passive"))
    )
    (net (code "61") (name "Net-(DD3-OSCI)") (class "Default")
      (node (ref "C11") (pin "2") (pinfunction "2_2") (pintype "passive"))
      (node (ref "DD3") (pin "1") (pinfunction "OSCI_1") (pintype "passive"))
      (node (ref "ZQ1") (pin "1") (pinfunction "1_1") (pintype "passive"))
    )
    (net (code "62") (name "Net-(DD3-OSCO)") (class "Default")
      (node (ref "C12") (pin "2") (pinfunction "2_2") (pintype "passive"))
      (node (ref "DD3") (pin "2") (pinfunction "OSCO_2") (pintype "passive"))
      (node (ref "ZQ1") (pin "2") (pinfunction "2_2") (pintype "passive"))
    )
    (net (code "63") (name "Net-(DD3-VDD)") (class "Default")
      (node (ref "C14") (pin "1") (pinfunction "1_1") (pintype "passive"))
      (node (ref "DD3") (pin "8") (pinfunction "VDD_8") (pintype "power_in"))
      (node (ref "R29") (pin "1") (pinfunction "1_1") (pintype "passive"))
      (node (ref "VD1") (pin "C") (pinfunction "C_C") (pintype "passive"))
    )
    (net (code "64") (name "Net-(HA1-Pad1)") (class "Default")
      (node (ref "HA1") (pin "1") (pintype "passive"))
      (node (ref "R30") (pin "1") (pinfunction "1_1") (pintype "passive"))
    )
    (net (code "65") (name "Net-(HL15-PadA)") (class "Default")
      (node (ref "HL15") (pin "A") (pinfunction "A_A") (pintype "passive"))
      (node (ref "R14") (pin "1") (pinfunction "1_1") (pintype "passive"))
    )
    (net (code "66") (name "Net-(HL16-PadA)") (class "Default")
      (node (ref "HL16") (pin "A") (pinfunction "A_A") (pintype "passive"))
      (node (ref "R15") (pin "1") (pinfunction "1_1") (pintype "passive"))
    )
    (net (code "67") (name "Net-(HL17-PadA)") (class "Default")
      (node (ref "HL17") (pin "A") (pinfunction "A_A") (pintype "passive"))
      (node (ref "R16") (pin "1") (pinfunction "1_1") (pintype "passive"))
    )
    (net (code "68") (name "Net-(HL18-PadA)") (class "Default")
      (node (ref "HL18") (pin "A") (pinfunction "A_A") (pintype "passive"))
      (node (ref "R17") (pin "1") (pinfunction "1_1") (pintype "passive"))
    )
    (net (code "69") (name "Net-(HL19-PadA)") (class "Default")
      (node (ref "HL19") (pin "A") (pinfunction "A_A") (pintype "passive"))
      (node (ref "R18") (pin "1") (pinfunction "1_1") (pintype "passive"))
    )
    (net (code "70") (name "Net-(R24-Pad1)") (class "Default")
      (node (ref "R24") (pin "1") (pinfunction "1_1") (pintype "passive"))
      (node (ref "SW1") (pin "1") (pinfunction "1_1") (pintype "passive"))
    )
    (net (code "71") (name "Net-(R25-Pad1)") (class "Default")
      (node (ref "R25") (pin "1") (pinfunction "1_1") (pintype "passive"))
      (node (ref "SW2") (pin "1") (pinfunction "1_1") (pintype "passive"))
    )
    (net (code "72") (name "Net-(R28-Pad1)") (class "Default")
      (node (ref "R28") (pin "1") (pinfunction "1_1") (pintype "passive"))
      (node (ref "SW3") (pin "1") (pinfunction "1_1") (pintype "passive"))
    )
    (net (code "73") (name "Net-(R31-Pad1)") (class "Default")
      (node (ref "R31") (pin "1") (pinfunction "1_1") (pintype "passive"))
      (node (ref "SW4") (pin "1") (pinfunction "1_1") (pintype "passive"))
    )
    (net (code "74") (name "Net-(VT1-D)") (class "Default")
      (node (ref "HL1") (pin "C") (pinfunction "C_C") (pintype "passive"))
      (node (ref "HL11") (pin "C") (pinfunction "C_C") (pintype "passive"))
      (node (ref "HL13") (pin "C") (pinfunction "C_C") (pintype "passive"))
      (node (ref "HL3") (pin "C") (pinfunction "C_C") (pintype "passive"))
      (node (ref "HL5") (pin "C") (pinfunction "C_C") (pintype "passive"))
      (node (ref "HL7") (pin "C") (pinfunction "C_C") (pintype "passive"))
      (node (ref "HL9") (pin "C") (pinfunction "C_C") (pintype "passive"))
      (node (ref "VT1") (pin "Y") (pinfunction "D_Y") (pintype "passive"))
    )
    (net (code "75") (name "Net-(VT1-G)") (class "Default")
      (node (ref "R10") (pin "1") (pinfunction "1_1") (pintype "passive"))
      (node (ref "R13") (pin "2") (pinfunction "2_2") (pintype "passive"))
      (node (ref "VT1") (pin "X") (pinfunction "G_X") (pintype "passive"))
    )
    (net (code "76") (name "Net-(VT2-D)") (class "Default")
      (node (ref "HL10") (pin "C") (pinfunction "C_C") (pintype "passive"))
      (node (ref "HL12") (pin "C") (pinfunction "C_C") (pintype "passive"))
      (node (ref "HL14") (pin "C") (pinfunction "C_C") (pintype "passive"))
      (node (ref "HL2") (pin "C") (pinfunction "C_C") (pintype "passive"))
      (node (ref "HL4") (pin "C") (pinfunction "C_C") (pintype "passive"))
      (node (ref "HL6") (pin "C") (pinfunction "C_C") (pintype "passive"))
      (node (ref "HL8") (pin "C") (pinfunction "C_C") (pintype "passive"))
      (node (ref "VT2") (pin "Y") (pinfunction "D_Y") (pintype "passive"))
    )
    (net (code "77") (name "Net-(VT2-G)") (class "Default")
      (node (ref "R11") (pin "1") (pinfunction "1_1") (pintype "passive"))
      (node (ref "R12") (pin "2") (pinfunction "2_2") (pintype "passive"))
      (node (ref "VT2") (pin "X") (pinfunction "G_X") (pintype "passive"))
    )
    (net (code "78") (name "VCC") (class "Default")
      (node (ref "C3") (pin "2") (pinfunction "2_2") (pintype "passive"))
      (node (ref "C7") (pin "2") (pinfunction "2_2") (pintype "passive"))
      (node (ref "DA1") (pin "Z") (pinfunction "IN_Z") (pintype "passive"))
      (node (ref "DA3") (pin "6") (pinfunction "VCCB_6") (pintype "passive"))
      (node (ref "DD1") (pin "16") (pinfunction "VCC_16") (pintype "power_in"))
      (node (ref "DD2") (pin "16") (pinfunction "VCC_16") (pintype "power_in"))
      (node (ref "HL20") (pin "+") (pinfunction "VDD_+") (pintype "passive"))
      (node (ref "HL21") (pin "+") (pinfunction "VDD_+") (pintype "passive"))
      (node (ref "HL22") (pin "+") (pinfunction "VDD_+") (pintype "passive"))
      (node (ref "R2") (pin "1") (pinfunction "1_1") (pintype "passive"))
      (node (ref "R35") (pin "2") (pinfunction "2_2") (pintype "passive"))
      (node (ref "VD1") (pin "A") (pinfunction "A_A") (pintype "passive"))
      (node (ref "XS1") (pin "1") (pinfunction "1_1") (pintype "passive"))
    )
    (net (code "79") (name "unconnected-(A1-IO2-Pad24)") (class "Default")
      (node (ref "A1") (pin "24") (pinfunction "IO2_24") (pintype "bidirectional"))
    )
    (net (code "80") (name "unconnected-(A1-IO12-Pad14)") (class "Default")
      (node (ref "A1") (pin "14") (pinfunction "IO12_14") (pintype "bidirectional"))
    )
    (net (code "81") (name "unconnected-(A1-IO14-Pad13)") (class "Default")
      (node (ref "A1") (pin "13") (pinfunction "IO14_13") (pintype "bidirectional"))
    )
    (net (code "82") (name "unconnected-(A1-IO15-Pad23)") (class "Default")
      (node (ref "A1") (pin "23") (pinfunction "IO15_23") (pintype "bidirectional"))
    )
    (net (code "83") (name "unconnected-(A1-IO34-Pad6)") (class "Default")
      (node (ref "A1") (pin "6") (pinfunction "IO34_6") (pintype "input"))
    )
    (net (code "84") (name "unconnected-(A1-IO35-Pad7)") (class "Default")
      (node (ref "A1") (pin "7") (pinfunction "IO35_7") (pintype "input"))
    )
    (net (code "85") (name "unconnected-(A1-NC-Pad32)") (class "Default")
      (node (ref "A1") (pin "32") (pinfunction "NC_32") (pintype "bidirectional"))
    )
    (net (code "86") (name "unconnected-(A1-SCK{slash}CLK-Pad20)") (class "Default")
      (node (ref "A1") (pin "20") (pinfunction "SCK/CLK_20") (pintype "bidirectional"))
    )
    (net (code "87") (name "unconnected-(A1-SCS{slash}CMD-Pad19)") (class "Default")
      (node (ref "A1") (pin "19") (pinfunction "SCS/CMD_19") (pintype "bidirectional"))
    )
    (net (code "88") (name "unconnected-(A1-SDI{slash}SD1-Pad22)") (class "Default")
      (node (ref "A1") (pin "22") (pinfunction "SDI/SD1_22") (pintype "bidirectional"))
    )
    (net (code "89") (name "unconnected-(A1-SDO{slash}SD0-Pad21)") (class "Default")
      (node (ref "A1") (pin "21") (pinfunction "SDO/SD0_21") (pintype "bidirectional"))
    )
    (net (code "90") (name "unconnected-(A1-SENSOR_VN-Pad5)") (class "Default")
      (node (ref "A1") (pin "5") (pinfunction "SENSOR_VN_5") (pintype "input"))
    )
    (net (code "91") (name "unconnected-(A1-SENSOR_VP-Pad4)") (class "Default")
      (node (ref "A1") (pin "4") (pinfunction "SENSOR_VP_4") (pintype "input"))
    )
    (net (code "92") (name "unconnected-(A1-SHD{slash}SD2-Pad17)") (class "Default")
      (node (ref "A1") (pin "17") (pinfunction "SHD/SD2_17") (pintype "bidirectional"))
    )
    (net (code "93") (name "unconnected-(A1-SWP{slash}SD3-Pad18)") (class "Default")
      (node (ref "A1") (pin "18") (pinfunction "SWP/SD3_18") (pintype "bidirectional"))
    )
    (net (code "94") (name "unconnected-(DD1-Q0-Pad15)") (class "Default")
      (node (ref "DD1") (pin "15") (pinfunction "Q0_15") (pintype "output"))
    )
    (net (code "95") (name "unconnected-(DD2-Q0-Pad15)") (class "Default")
      (node (ref "DD2") (pin "15") (pinfunction "Q0_15") (pintype "output"))
    )
    (net (code "96") (name "unconnected-(DD2-Q6-Pad6)") (class "Default")
      (node (ref "DD2") (pin "6") (pinfunction "Q6_6") (pintype "output"))
    )
    (net (code "97") (name "unconnected-(DD2-Q7-Pad7)") (class "Default")
      (node (ref "DD2") (pin "7") (pinfunction "Q7_7") (pintype "output"))
    )
    (net (code "98") (name "unconnected-(DD2-Q7S-Pad9)") (class "Default")
      (node (ref "DD2") (pin "9") (pinfunction "Q7S_9") (pintype "output"))
    )
    (net (code "99") (name "unconnected-(DD3-CLKOUT-Pad7)") (class "Default")
      (node (ref "DD3") (pin "7") (pinfunction "CLKOUT_7") (pintype "output"))
    )
    (net (code "100") (name "unconnected-(DD3-~{INT}-Pad3)") (class "Default")
      (node (ref "DD3") (pin "3") (pinfunction "~{INT}_3") (pintype "output"))
    )
    (net (code "101") (name "unconnected-(HL20-DO-PadO)") (class "Default")
      (node (ref "HL20") (pin "O") (pinfunction "DO_O") (pintype "passive"))
    )
    (net (code "102") (name "unconnected-(HL21-DO-PadO)") (class "Default")
      (node (ref "HL21") (pin "O") (pinfunction "DO_O") (pintype "passive"))
    )
    (net (code "103") (name "unconnected-(HL22-DO-PadO)") (class "Default")
      (node (ref "HL22") (pin "O") (pinfunction "DO_O") (pintype "passive"))
    )
  )
)
